# AngleMod_V1.net
KiCad netlist of a schematic drawn in Altium Designer
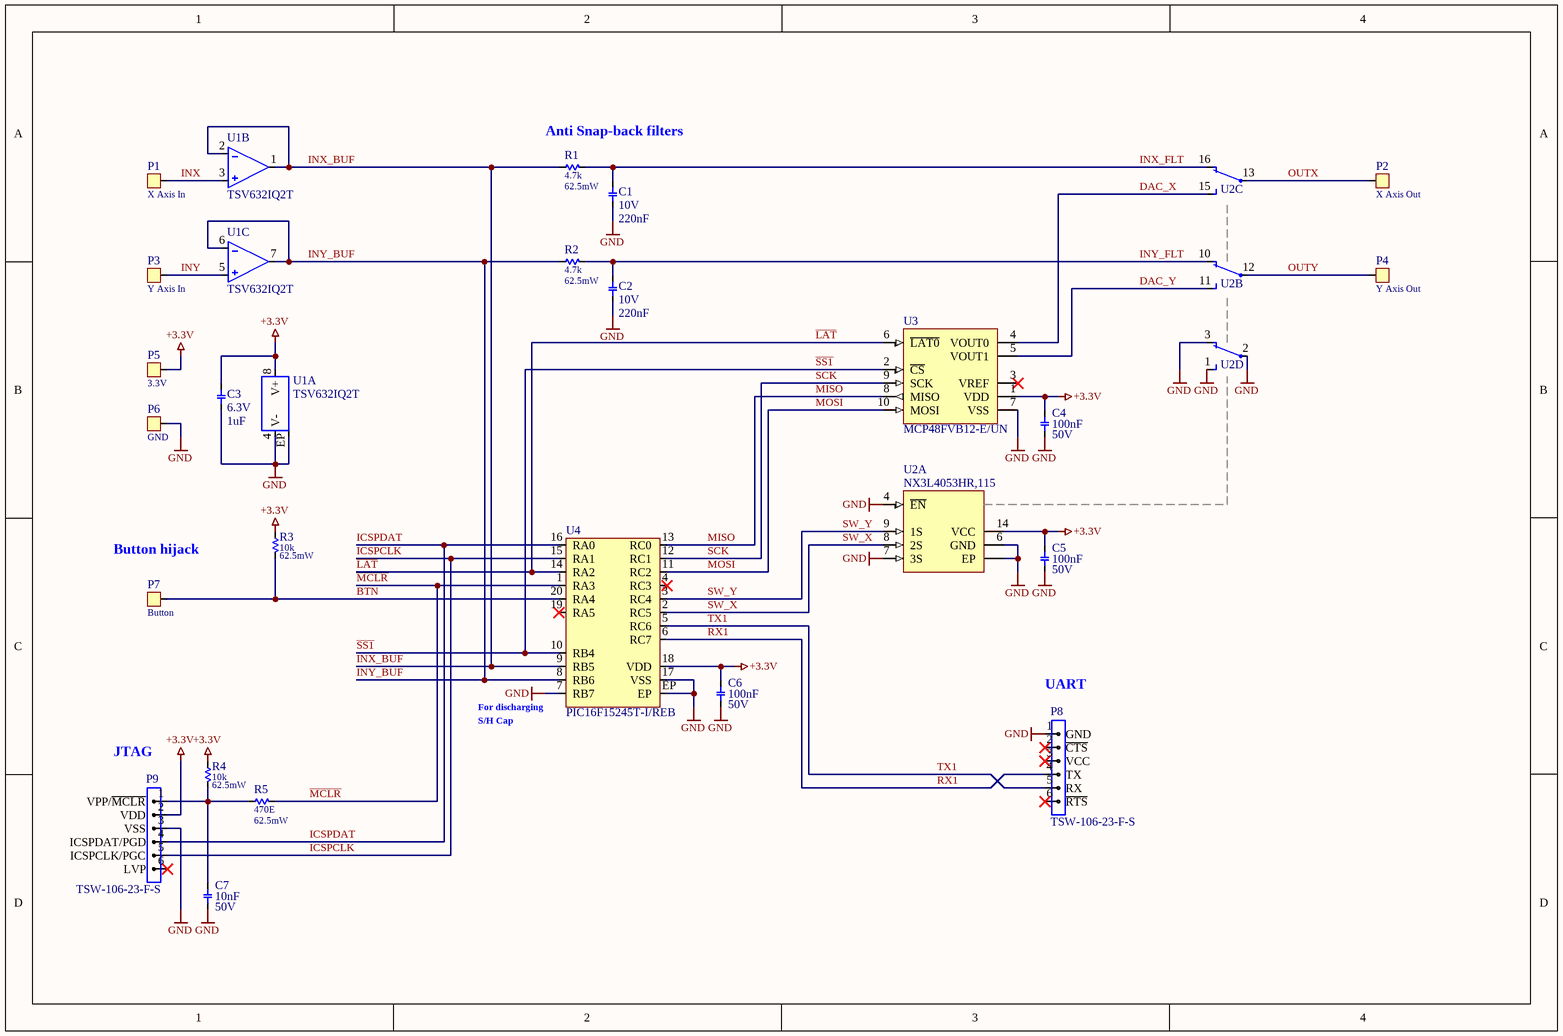
[diagram p0: AngleMod V1.SchDoc]

(export (version "E")
  (design (tool "Eeschema 10.0.6"))
  (components
    (comp (ref "C1")
      (value "220nF")
      (footprint "CX7R0603K")
      (description "0.22 µF ±10% 10V Ceramic Capacitor X7R 0603 (1608 Metric)")
      (fields (field (name "VALUE2") "10V") (field (name "Comment") "CC0603KRX7R6BB224"))
      (libsource (lib "WalkMod") (part "kyocera-C-X7R-0603"))
    )
    (comp (ref "C2")
      (value "220nF")
      (footprint "CX7R0603K")
      (description "0.22 µF ±10% 10V Ceramic Capacitor X7R 0603 (1608 Metric)")
      (fields (field (name "VALUE2") "10V") (field (name "Comment") "CC0603KRX7R6BB224"))
      (libsource (lib "WalkMod") (part "kyocera-C-X7R-0603"))
    )
    (comp (ref "C3")
      (value "1uF")
      (footprint "CX7R0603K")
      (description "SMD Capacitor")
      (fields (field (name "VALUE2") "6.3V") (field (name "Comment") "06036C105JAT2A"))
      (libsource (lib "WalkMod") (part "kyocera-C-X7R-0603"))
    )
    (comp (ref "C4")
      (value "100nF")
      (footprint "CX7R0402C")
      (description "SMD Capacitor")
      (fields (field (name "VALUE2") "50V") (field (name "Comment") "04025C104JAT2A"))
      (libsource (lib "WalkMod") (part "kyocera-C-X7R-0402"))
    )
    (comp (ref "C5")
      (value "100nF")
      (footprint "CX7R0402C")
      (description "SMD Capacitor")
      (fields (field (name "VALUE2") "50V") (field (name "Comment") "04025C104JAT2A"))
      (libsource (lib "WalkMod") (part "kyocera-C-X7R-0402"))
    )
    (comp (ref "C6")
      (value "100nF")
      (footprint "CX7R0402C")
      (description "SMD Capacitor")
      (fields (field (name "VALUE2") "50V") (field (name "Comment") "04025C104JAT2A"))
      (libsource (lib "WalkMod") (part "kyocera-C-X7R-0402"))
    )
    (comp (ref "C7")
      (value "10nF")
      (footprint "CX7R0402C")
      (description "SMD Capacitor")
      (fields (field (name "VALUE2") "50V") (field (name "Comment") "04025C104JAT2A"))
      (libsource (lib "WalkMod") (part "kyocera-C-X7R-0402"))
    )
    (comp (ref "P1")
      (value "SMD Pad 1 pin")
      (footprint "PAD_2X1.5_SQUARE")
      (description "Single SMD Pad")
      (fields (field (name "NAME") "X Axis In"))
      (libsource (lib "") (part "SMD Pad 1 pin_1"))
    )
    (comp (ref "P2")
      (value "SMD Pad 1 pin")
      (footprint "PAD_2X1.5_SQUARE")
      (description "Single SMD Pad")
      (fields (field (name "NAME") "X Axis Out"))
      (libsource (lib "WalkMod") (part "SMD Pad 1 pin"))
    )
    (comp (ref "P3")
      (value "SMD Pad 1 pin")
      (footprint "PAD_2X1.5_SQUARE")
      (description "Single SMD Pad")
      (fields (field (name "NAME") "Y Axis In"))
      (libsource (lib "") (part "SMD Pad 1 pin_1"))
    )
    (comp (ref "P4")
      (value "SMD Pad 1 pin")
      (footprint "PAD_2X1.5_SQUARE")
      (description "Single SMD Pad")
      (fields (field (name "NAME") "Y Axis Out"))
      (libsource (lib "WalkMod") (part "SMD Pad 1 pin"))
    )
    (comp (ref "P5")
      (value "SMD Pad 1 pin")
      (footprint "PAD_2X1.5_SQUARE")
      (description "Single SMD Pad")
      (fields (field (name "NAME") "3.3V"))
      (libsource (lib "") (part "SMD Pad 1 pin_1"))
    )
    (comp (ref "P6")
      (value "SMD Pad 1 pin")
      (footprint "PAD_2X1.5_SQUARE")
      (description "Single SMD Pad")
      (fields (field (name "NAME") "GND"))
      (libsource (lib "") (part "SMD Pad 1 pin_1"))
    )
    (comp (ref "P7")
      (value "SMD Pad 1 pin")
      (footprint "PAD_2X1.5_SQUARE")
      (description "Single SMD Pad")
      (fields (field (name "NAME") "Button"))
      (libsource (lib "") (part "SMD Pad 1 pin_1"))
    )
    (comp (ref "P8")
      (value "TSW-106-23-F-S")
      (footprint "TSW-106-23-F-S_SIDEA")
      (description "Connector Header Through Hole 6 position 0.100\" (2.54mm)")
      (libsource (lib "WalkMod") (part "TSW-106-23-F-S"))
    )
    (comp (ref "P9")
      (value "TSW-106-23-F-S")
      (footprint "TSW-106-23-F-S_SIDEA")
      (description "Connector Header Through Hole 6 position 0.100\" (2.54mm)")
      (libsource (lib "WalkMod") (part "TSW-106-23-F-S"))
    )
    (comp (ref "R1")
      (value "4.7k")
      (footprint "RT0402_C")
      (fields (field (name "VALUE2") "62.5mW") (field (name "Comment") "RG1005P-472-B-T5"))
      (libsource (lib "WalkMod") (part "RT0402DRD0747KL"))
    )
    (comp (ref "R2")
      (value "4.7k")
      (footprint "RT0402_C")
      (fields (field (name "VALUE2") "62.5mW") (field (name "Comment") "RG1005P-472-B-T5"))
      (libsource (lib "WalkMod") (part "RT0402DRD0747KL"))
    )
    (comp (ref "R3")
      (value "10k")
      (footprint "RT0402_C")
      (fields (field (name "VALUE2") "62.5mW") (field (name "Comment") "TBD"))
      (libsource (lib "WalkMod") (part "RT0402DRD0747KL"))
    )
    (comp (ref "R4")
      (value "10k")
      (footprint "RT0402_C")
      (fields (field (name "VALUE2") "62.5mW") (field (name "Comment") "TBD"))
      (libsource (lib "WalkMod") (part "RT0402DRD0747KL"))
    )
    (comp (ref "R5")
      (value "470E")
      (footprint "RT0402_C")
      (fields (field (name "VALUE2") "62.5mW") (field (name "Comment") "TBD"))
      (libsource (lib "WalkMod") (part "RT0402DRD0747KL"))
    )
    (comp (ref "U1")
      (value "TSV632IQ2T")
      (footprint "DFN-8_2X2_0.5_C")
      (description "General Purpose Amplifier 2 Circuit Rail-to-Rail 8-DFN (2x2)")
      (libsource (lib "WalkMod") (part "TSV632IQ2T"))
    )
    (comp (ref "U2")
      (value "NX3L4053HR,115")
      (footprint "HXQFN-16_SOT-1039-2_C")
      (description "3 Circuit IC Switch 2:1 800mOhm 16-HXQFN (3x3)")
      (libsource (lib "") (part "NX3L4053_1"))
    )
    (comp (ref "U3")
      (value "MCP48FVB12-E/UN")
      (footprint "MSOP-10_0.5_C")
      (libsource (lib "WalkMod") (part "MCP48FVB12-E/UN"))
    )
    (comp (ref "U4")
      (value "PIC16F15245T-I/REB")
      (footprint "VQFN-20_0.4_C")
      (libsource (lib "WalkMod") (part "PIC16F15245T-I/REB"))
    )
  )
  (nets
    (net (code "1") (name "+3.3V") (class "Default")
      (node (ref "C3") (pin "2") (pinfunction "2_2") (pintype "passive"))
      (node (ref "C4") (pin "2") (pinfunction "2_2") (pintype "passive"))
      (node (ref "C5") (pin "2") (pinfunction "2_2") (pintype "passive"))
      (node (ref "C6") (pin "2") (pinfunction "2_2") (pintype "passive"))
      (node (ref "P5") (pin "1") (pinfunction "1_1") (pintype "passive"))
      (node (ref "P9") (pin "2") (pinfunction "VDD_2") (pintype "passive"))
      (node (ref "R3") (pin "2") (pinfunction "2_2") (pintype "passive"))
      (node (ref "R4") (pin "2") (pinfunction "2_2") (pintype "passive"))
      (node (ref "U1") (pin "8") (pinfunction "V+_8") (pintype "passive"))
      (node (ref "U2") (pin "14") (pinfunction "VCC_14") (pintype "power_in"))
      (node (ref "U3") (pin "1") (pinfunction "VDD_1") (pintype "power_in"))
      (node (ref "U4") (pin "18") (pinfunction "VDD_18") (pintype "passive"))
    )
    (net (code "2") (name "/BTN") (class "Default")
      (node (ref "P7") (pin "1") (pinfunction "1_1") (pintype "passive"))
      (node (ref "R3") (pin "1") (pinfunction "1_1") (pintype "passive"))
      (node (ref "U4") (pin "20") (pinfunction "RA4_20") (pintype "passive"))
    )
    (net (code "3") (name "/DAC_X") (class "Default")
      (node (ref "U2") (pin "15") (pinfunction "2Y1_15") (pintype "passive"))
      (node (ref "U3") (pin "4") (pinfunction "VOUT0_4") (pintype "passive"))
    )
    (net (code "4") (name "/DAC_Y") (class "Default")
      (node (ref "U2") (pin "11") (pinfunction "1Y1_11") (pintype "passive"))
      (node (ref "U3") (pin "5") (pinfunction "VOUT1_5") (pintype "passive"))
    )
    (net (code "5") (name "/ICSPCLK") (class "Default")
      (node (ref "P9") (pin "5") (pinfunction "ICSPCLK/PGC_5") (pintype "passive"))
      (node (ref "U4") (pin "15") (pinfunction "RA1_15") (pintype "passive"))
    )
    (net (code "6") (name "/ICSPDAT") (class "Default")
      (node (ref "P9") (pin "4") (pinfunction "ICSPDAT/PGD_4") (pintype "passive"))
      (node (ref "U4") (pin "16") (pinfunction "RA0_16") (pintype "passive"))
    )
    (net (code "7") (name "/INX") (class "Default")
      (node (ref "P1") (pin "1") (pinfunction "1_1") (pintype "passive"))
      (node (ref "U1") (pin "3") (pinfunction "IN1+_3") (pintype "passive"))
    )
    (net (code "8") (name "/INX_BUF") (class "Default")
      (node (ref "R1") (pin "2") (pinfunction "2_2") (pintype "passive"))
      (node (ref "U1") (pin "1") (pinfunction "OUT1_1") (pintype "passive"))
      (node (ref "U1") (pin "2") (pinfunction "IN1-_2") (pintype "passive"))
      (node (ref "U4") (pin "9") (pinfunction "RB5_9") (pintype "passive"))
    )
    (net (code "9") (name "/INX_FLT") (class "Default")
      (node (ref "C1") (pin "2") (pinfunction "2_2") (pintype "passive"))
      (node (ref "R1") (pin "1") (pinfunction "1_1") (pintype "passive"))
      (node (ref "U2") (pin "16") (pinfunction "2Y0_16") (pintype "passive"))
    )
    (net (code "10") (name "/INY") (class "Default")
      (node (ref "P3") (pin "1") (pinfunction "1_1") (pintype "passive"))
      (node (ref "U1") (pin "5") (pinfunction "IN2+_5") (pintype "passive"))
    )
    (net (code "11") (name "/INY_BUF") (class "Default")
      (node (ref "R2") (pin "2") (pinfunction "2_2") (pintype "passive"))
      (node (ref "U1") (pin "6") (pinfunction "IN2-_6") (pintype "passive"))
      (node (ref "U1") (pin "7") (pinfunction "OUT2_7") (pintype "passive"))
      (node (ref "U4") (pin "8") (pinfunction "RB6_8") (pintype "passive"))
    )
    (net (code "12") (name "/INY_FLT") (class "Default")
      (node (ref "C2") (pin "2") (pinfunction "2_2") (pintype "passive"))
      (node (ref "R2") (pin "1") (pinfunction "1_1") (pintype "passive"))
      (node (ref "U2") (pin "10") (pinfunction "1Y0_10") (pintype "passive"))
    )
    (net (code "13") (name "/MISO") (class "Default")
      (node (ref "U3") (pin "8") (pinfunction "MISO_8") (pintype "output"))
      (node (ref "U4") (pin "13") (pinfunction "RC0_13") (pintype "passive"))
    )
    (net (code "14") (name "/MOSI") (class "Default")
      (node (ref "U3") (pin "10") (pinfunction "MOSI_10") (pintype "input"))
      (node (ref "U4") (pin "11") (pinfunction "RC2_11") (pintype "passive"))
    )
    (net (code "15") (name "/OUTX") (class "Default")
      (node (ref "P2") (pin "1") (pinfunction "1_1") (pintype "passive"))
      (node (ref "U2") (pin "13") (pinfunction "2Z_13") (pintype "passive"))
    )
    (net (code "16") (name "/OUTY") (class "Default")
      (node (ref "P4") (pin "1") (pinfunction "1_1") (pintype "passive"))
      (node (ref "U2") (pin "12") (pinfunction "1Z_12") (pintype "passive"))
    )
    (net (code "17") (name "/RX1") (class "Default")
      (node (ref "P8") (pin "4") (pinfunction "ICSPDAT/PGD_4") (pintype "passive"))
      (node (ref "U4") (pin "6") (pinfunction "RC7_6") (pintype "passive"))
    )
    (net (code "18") (name "/SCK") (class "Default")
      (node (ref "U3") (pin "9") (pinfunction "SCK_9") (pintype "input"))
      (node (ref "U4") (pin "12") (pinfunction "RC1_12") (pintype "passive"))
    )
    (net (code "19") (name "/SW_X") (class "Default")
      (node (ref "U2") (pin "8") (pinfunction "2S_8") (pintype "input"))
      (node (ref "U4") (pin "2") (pinfunction "RC5_2") (pintype "passive"))
    )
    (net (code "20") (name "/SW_Y") (class "Default")
      (node (ref "U2") (pin "9") (pinfunction "1S_9") (pintype "input"))
      (node (ref "U4") (pin "3") (pinfunction "RC4_3") (pintype "passive"))
    )
    (net (code "21") (name "/TX1") (class "Default")
      (node (ref "P8") (pin "5") (pinfunction "ICSPCLK/PGC_5") (pintype "passive"))
      (node (ref "U4") (pin "5") (pinfunction "RC6_5") (pintype "passive"))
    )
    (net (code "22") (name "/~{LAT}") (class "Default")
      (node (ref "U3") (pin "6") (pinfunction "~{LAT0}_6") (pintype "input"))
      (node (ref "U4") (pin "14") (pinfunction "RA2_14") (pintype "passive"))
    )
    (net (code "23") (name "/~{MCLR}") (class "Default")
      (node (ref "R5") (pin "1") (pinfunction "1_1") (pintype "passive"))
      (node (ref "U4") (pin "1") (pinfunction "RA3_1") (pintype "passive"))
    )
    (net (code "24") (name "/~{SS1}") (class "Default")
      (node (ref "U3") (pin "2") (pinfunction "~{CS}_2") (pintype "input"))
      (node (ref "U4") (pin "10") (pinfunction "RB4_10") (pintype "passive"))
    )
    (net (code "25") (name "GND") (class "Default")
      (node (ref "C1") (pin "1") (pinfunction "1_1") (pintype "passive"))
      (node (ref "C2") (pin "1") (pinfunction "1_1") (pintype "passive"))
      (node (ref "C3") (pin "1") (pinfunction "1_1") (pintype "passive"))
      (node (ref "C4") (pin "1") (pinfunction "1_1") (pintype "passive"))
      (node (ref "C5") (pin "1") (pinfunction "1_1") (pintype "passive"))
      (node (ref "C6") (pin "1") (pinfunction "1_1") (pintype "passive"))
      (node (ref "C7") (pin "1") (pinfunction "1_1") (pintype "passive"))
      (node (ref "P6") (pin "1") (pinfunction "1_1") (pintype "passive"))
      (node (ref "P8") (pin "1") (pinfunction "VPP/~{MCLR}_1") (pintype "passive"))
      (node (ref "P9") (pin "3") (pinfunction "VSS_3") (pintype "passive"))
      (node (ref "U1") (pin "4") (pinfunction "V-_4") (pintype "passive"))
      (node (ref "U1") (pin "EP") (pinfunction "EP_EP") (pintype "passive"))
      (node (ref "U2") (pin "1") (pinfunction "3Y1_1") (pintype "passive"))
      (node (ref "U2") (pin "2") (pinfunction "3Z_2") (pintype "passive"))
      (node (ref "U2") (pin "3") (pinfunction "3Y0_3") (pintype "passive"))
      (node (ref "U2") (pin "4") (pinfunction "~{EN}_4") (pintype "input"))
      (node (ref "U2") (pin "6") (pinfunction "GND_6") (pintype "power_in"))
      (node (ref "U2") (pin "7") (pinfunction "3S_7") (pintype "input"))
      (node (ref "U2") (pin "EP") (pinfunction "EP_EP") (pintype "power_in"))
      (node (ref "U3") (pin "7") (pinfunction "VSS_7") (pintype "power_in"))
      (node (ref "U4") (pin "17") (pinfunction "VSS_17") (pintype "passive"))
      (node (ref "U4") (pin "7") (pinfunction "RB7_7") (pintype "passive"))
      (node (ref "U4") (pin "EP") (pinfunction "EP_EP") (pintype "passive"))
    )
    (net (code "26") (name "Net-(P9-VPP{slash}~{MCLR})") (class "Default")
      (node (ref "C7") (pin "2") (pinfunction "2_2") (pintype "passive"))
      (node (ref "P9") (pin "1") (pinfunction "VPP/~{MCLR}_1") (pintype "passive"))
      (node (ref "R4") (pin "1") (pinfunction "1_1") (pintype "passive"))
      (node (ref "R5") (pin "2") (pinfunction "2_2") (pintype "passive"))
    )
    (net (code "27") (name "unconnected-(P8-LVP-Pad6)") (class "Default")
      (node (ref "P8") (pin "6") (pinfunction "LVP_6") (pintype "passive+no_connect"))
    )
    (net (code "28") (name "unconnected-(P8-VDD-Pad2)") (class "Default")
      (node (ref "P8") (pin "2") (pinfunction "VDD_2") (pintype "passive+no_connect"))
    )
    (net (code "29") (name "unconnected-(P8-VSS-Pad3)") (class "Default")
      (node (ref "P8") (pin "3") (pinfunction "VSS_3") (pintype "passive+no_connect"))
    )
    (net (code "30") (name "unconnected-(P9-LVP-Pad6)") (class "Default")
      (node (ref "P9") (pin "6") (pinfunction "LVP_6") (pintype "passive+no_connect"))
    )
    (net (code "31") (name "unconnected-(U3-VREF-Pad3)") (class "Default")
      (node (ref "U3") (pin "3") (pinfunction "VREF_3") (pintype "passive+no_connect"))
    )
    (net (code "32") (name "unconnected-(U4-RA5-Pad19)") (class "Default")
      (node (ref "U4") (pin "19") (pinfunction "RA5_19") (pintype "passive+no_connect"))
    )
    (net (code "33") (name "unconnected-(U4-RC3-Pad4)") (class "Default")
      (node (ref "U4") (pin "4") (pinfunction "RC3_4") (pintype "passive+no_connect"))
    )
  )
)
